# Temp_Controller.net
KiCad netlist of a schematic drawn in EAGLE
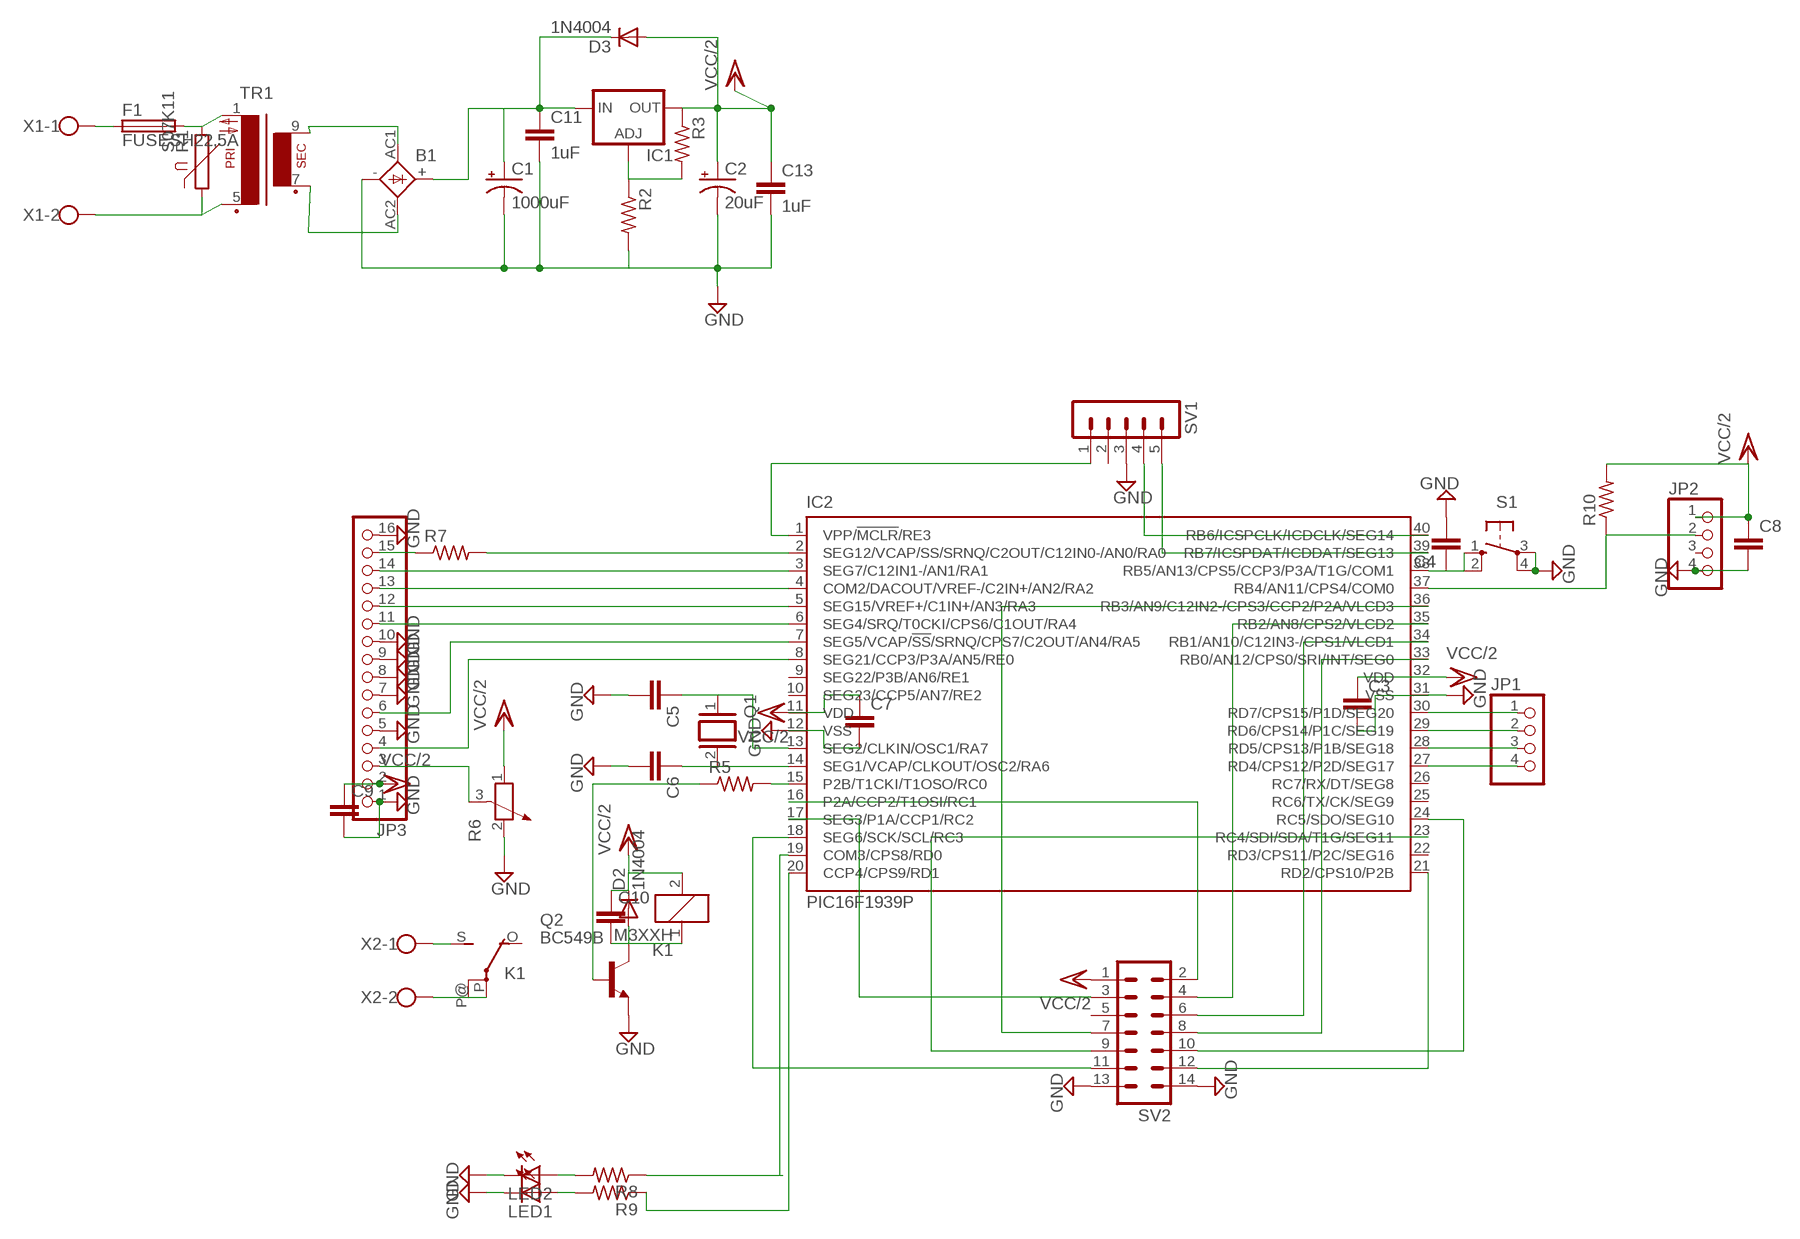
[diagram p0: schematic, sheet 1]

(export (version "E")
  (design (tool "Eeschema 10.0.6"))
  (components
    (comp (ref "B1")
      (value "1KAB")
      (footprint "eagle-import:1KAB")
      (libsource (lib "eagle-import") (part "1KAB"))
    )
    (comp (ref "C1")
      (value "1000uF")
      (footprint "eagle-import:E5-13")
      (libsource (lib "eagle-import") (part "CPOL-USE5-13"))
    )
    (comp (ref "C2")
      (value "20uF")
      (footprint "eagle-import:E5-6")
      (libsource (lib "eagle-import") (part "CPOL-USE5-6"))
    )
    (comp (ref "C3")
      (value "C-EU025-030X050")
      (footprint "eagle-import:C025-030X050")
      (libsource (lib "eagle-import") (part "C-EU025-030X050"))
    )
    (comp (ref "C4")
      (value "C-EU025-030X050")
      (footprint "eagle-import:C025-030X050")
      (libsource (lib "eagle-import") (part "C-EU025-030X050"))
    )
    (comp (ref "C5")
      (value "C2.5/2")
      (footprint "eagle-import:C2.5-2")
      (libsource (lib "eagle-import") (part "C2.5/2"))
    )
    (comp (ref "C6")
      (value "C2.5/2")
      (footprint "eagle-import:C2.5-2")
      (libsource (lib "eagle-import") (part "C2.5/2"))
    )
    (comp (ref "C7")
      (value "C-EU025-030X050")
      (footprint "eagle-import:C025-030X050")
      (libsource (lib "eagle-import") (part "C-EU025-030X050"))
    )
    (comp (ref "C8")
      (value "C-EU025-030X050")
      (footprint "eagle-import:C025-030X050")
      (libsource (lib "eagle-import") (part "C-EU025-030X050"))
    )
    (comp (ref "C9")
      (value "C-EU025-030X050")
      (footprint "eagle-import:C025-030X050")
      (libsource (lib "eagle-import") (part "C-EU025-030X050"))
    )
    (comp (ref "C10")
      (value "C-EU025-030X050")
      (footprint "eagle-import:C025-030X050")
      (libsource (lib "eagle-import") (part "C-EU025-030X050"))
    )
    (comp (ref "C11")
      (value "1uF")
      (footprint "eagle-import:C025-030X050")
      (libsource (lib "eagle-import") (part "C-EU025-030X050"))
    )
    (comp (ref "C13")
      (value "1uF")
      (footprint "eagle-import:C025-030X050")
      (libsource (lib "eagle-import") (part "C-EU025-030X050"))
    )
    (comp (ref "D2")
      (value "1N4004")
      (footprint "eagle-import:DO41-10")
      (libsource (lib "eagle-import") (part "1N4004"))
    )
    (comp (ref "D3")
      (value "1N4004")
      (footprint "eagle-import:DO41-10")
      (libsource (lib "eagle-import") (part "1N4004"))
    )
    (comp (ref "F1")
      (value "FUSESH22,5A")
      (footprint "eagle-import:SH22,5A")
      (fields (field (name "OC_FARNELL") "unknown") (field (name "OC_NEWARK") "unknown"))
      (libsource (lib "eagle-import") (part "FUSESH22,5A"))
    )
    (comp (ref "IC1")
      (value "LM317TS")
      (footprint "eagle-import:317TS")
      (libsource (lib "eagle-import") (part "LM317TS"))
    )
    (comp (ref "IC2")
      (value "PIC16F1939P")
      (footprint "eagle-import:DIL40")
      (libsource (lib "eagle-import") (part "PIC16F193?P9"))
    )
    (comp (ref "JP1")
      (value "PINHD-1X4")
      (footprint "eagle-import:1X04")
      (libsource (lib "eagle-import") (part "PINHD-1X4"))
    )
    (comp (ref "JP2")
      (value "PINHD-1X4")
      (footprint "eagle-import:1X04")
      (libsource (lib "eagle-import") (part "PINHD-1X4"))
    )
    (comp (ref "JP3")
      (value "PINHD-1X16")
      (footprint "eagle-import:1X16")
      (libsource (lib "eagle-import") (part "PINHD-1X16"))
    )
    (comp (ref "K1")
      (value "M3XXH")
      (footprint "eagle-import:M3XXH")
      (libsource (lib "eagle-import") (part "M3XXH"))
    )
    (comp (ref "LED1")
      (value "LED3MM")
      (footprint "eagle-import:LED3MM")
      (libsource (lib "eagle-import") (part "LED3MM"))
    )
    (comp (ref "LED2")
      (value "LED3MM")
      (footprint "eagle-import:LED3MM")
      (libsource (lib "eagle-import") (part "LED3MM"))
    )
    (comp (ref "Q1")
      (value "XTAL/S")
      (footprint "eagle-import:QS")
      (libsource (lib "eagle-import") (part "XTAL/S"))
    )
    (comp (ref "Q2")
      (value "BC549B")
      (footprint "eagle-import:TO92-EBC")
      (libsource (lib "eagle-import") (part "BC549B"))
    )
    (comp (ref "R1")
      (value "S07K11")
      (footprint "eagle-import:S07K11")
      (libsource (lib "eagle-import") (part "S07K11"))
    )
    (comp (ref "R2")
      (value "R-US_0207/10")
      (footprint "eagle-import:0207_10")
      (libsource (lib "eagle-import") (part "R-US_0207/10"))
    )
    (comp (ref "R3")
      (value "R-US_0207/10")
      (footprint "eagle-import:0207_10")
      (libsource (lib "eagle-import") (part "R-US_0207/10"))
    )
    (comp (ref "R5")
      (value "R-US_0207/10")
      (footprint "eagle-import:0207_10")
      (libsource (lib "eagle-import") (part "R-US_0207/10"))
    )
    (comp (ref "R6")
      (value "POTENTIOMETER_PT-10")
      (footprint "eagle-import:PT-10")
      (libsource (lib "eagle-import") (part "POTENTIOMETER_PT-10"))
    )
    (comp (ref "R7")
      (value "R-US_0207/10")
      (footprint "eagle-import:0207_10")
      (libsource (lib "eagle-import") (part "R-US_0207/10"))
    )
    (comp (ref "R8")
      (value "R-US_0207/10")
      (footprint "eagle-import:0207_10")
      (libsource (lib "eagle-import") (part "R-US_0207/10"))
    )
    (comp (ref "R9")
      (value "R-US_0207/10")
      (footprint "eagle-import:0207_10")
      (libsource (lib "eagle-import") (part "R-US_0207/10"))
    )
    (comp (ref "R10")
      (value "R-US_0207/10")
      (footprint "eagle-import:0207_10")
      (libsource (lib "eagle-import") (part "R-US_0207/10"))
    )
    (comp (ref "S1")
      (value "10-XX")
      (footprint "eagle-import:B3F-10XX")
      (libsource (lib "eagle-import") (part "10-XX"))
    )
    (comp (ref "SV1")
      (value "MA05-1")
      (footprint "eagle-import:MA05-1")
      (libsource (lib "eagle-import") (part "MA05-1"))
    )
    (comp (ref "SV2")
      (value "MA07-2")
      (footprint "eagle-import:MA07-2")
      (libsource (lib "eagle-import") (part "MA07-2"))
    )
    (comp (ref "TR1")
      (value "VV11")
      (footprint "eagle-import:VV11")
      (libsource (lib "eagle-import") (part "VV11"))
    )
    (comp (ref "X1")
      (value "W237-02P")
      (footprint "eagle-import:W237-132")
      (libsource (lib "eagle-import") (part "W237-02P"))
    )
    (comp (ref "X2")
      (value "W237-02P")
      (footprint "eagle-import:W237-132")
      (libsource (lib "eagle-import") (part "W237-02P"))
    )
  )
  (nets
    (net (code "1") (name "GND") (class "Default")
      (node (ref "B1") (pin "-") (pinfunction "-_-") (pintype "passive"))
      (node (ref "C1") (pin "-") (pinfunction "-_-") (pintype "passive"))
      (node (ref "C11") (pin "2") (pinfunction "2_2") (pintype "passive"))
      (node (ref "C13") (pin "2") (pinfunction "2_2") (pintype "passive"))
      (node (ref "C2") (pin "-") (pinfunction "-_-") (pintype "passive"))
      (node (ref "C3") (pin "2") (pinfunction "2_2") (pintype "passive"))
      (node (ref "C4") (pin "2") (pinfunction "2_2") (pintype "passive"))
      (node (ref "C5") (pin "2") (pinfunction "2_2") (pintype "passive"))
      (node (ref "C6") (pin "2") (pinfunction "2_2") (pintype "passive"))
      (node (ref "C7") (pin "2") (pinfunction "2_2") (pintype "passive"))
      (node (ref "C8") (pin "2") (pinfunction "2_2") (pintype "passive"))
      (node (ref "C9") (pin "2") (pinfunction "2_2") (pintype "passive"))
      (node (ref "IC2") (pin "12") (pinfunction "VSS_12") (pintype "power_in"))
      (node (ref "IC2") (pin "31") (pinfunction "VSS_31") (pintype "power_in"))
      (node (ref "JP2") (pin "4") (pinfunction "4_4") (pintype "passive"))
      (node (ref "JP3") (pin "1") (pinfunction "1_1") (pintype "passive"))
      (node (ref "JP3") (pin "10") (pinfunction "10_10") (pintype "passive"))
      (node (ref "JP3") (pin "16") (pinfunction "16_16") (pintype "passive"))
      (node (ref "JP3") (pin "5") (pinfunction "5_5") (pintype "passive"))
      (node (ref "JP3") (pin "7") (pinfunction "7_7") (pintype "passive"))
      (node (ref "JP3") (pin "8") (pinfunction "8_8") (pintype "passive"))
      (node (ref "JP3") (pin "9") (pinfunction "9_9") (pintype "passive"))
      (node (ref "LED1") (pin "K") (pinfunction "C_K") (pintype "passive"))
      (node (ref "LED2") (pin "K") (pinfunction "C_K") (pintype "passive"))
      (node (ref "Q2") (pin "E") (pinfunction "E_E") (pintype "passive"))
      (node (ref "R2") (pin "2") (pinfunction "2_2") (pintype "passive"))
      (node (ref "R6") (pin "2") (pinfunction "2_2") (pintype "passive"))
      (node (ref "S1") (pin "3") (pinfunction "P_3") (pintype "passive"))
      (node (ref "S1") (pin "4") (pinfunction "P1_4") (pintype "passive"))
      (node (ref "SV1") (pin "3") (pinfunction "3_3") (pintype "passive"))
      (node (ref "SV2") (pin "13") (pinfunction "13_13") (pintype "passive"))
      (node (ref "SV2") (pin "14") (pinfunction "14_14") (pintype "passive"))
    )
    (net (code "2") (name "Net-(C10-Pad2)") (class "Default")
      (node (ref "C10") (pin "2") (pinfunction "2_2") (pintype "passive"))
      (node (ref "D2") (pin "A") (pinfunction "A_A") (pintype "passive"))
      (node (ref "K1") (pin "1") (pinfunction "1_1") (pintype "passive"))
      (node (ref "Q2") (pin "C") (pinfunction "C_C") (pintype "passive"))
    )
    (net (code "3") (name "Net-(IC1-ADJ)") (class "Default")
      (node (ref "IC1") (pin "1") (pinfunction "ADJ_1") (pintype "input"))
      (node (ref "R2") (pin "1") (pinfunction "1_1") (pintype "passive"))
      (node (ref "R3") (pin "2") (pinfunction "2_2") (pintype "passive"))
    )
    (net (code "4") (name "Net-(IC1-IN)") (class "Default")
      (node (ref "B1") (pin "+") (pinfunction "+_+") (pintype "passive"))
      (node (ref "C1") (pin "+") (pinfunction "+_+") (pintype "passive"))
      (node (ref "C11") (pin "1") (pinfunction "1_1") (pintype "passive"))
      (node (ref "D3") (pin "C") (pinfunction "C_C") (pintype "passive"))
      (node (ref "IC1") (pin "3") (pinfunction "IN_3") (pintype "input"))
    )
    (net (code "5") (name "Net-(IC2-CCP4{slash}CPS9{slash}RD1)") (class "Default")
      (node (ref "IC2") (pin "20") (pinfunction "CCP4/CPS9/RD1_20") (pintype "bidirectional"))
      (node (ref "R9") (pin "1") (pinfunction "1_1") (pintype "passive"))
    )
    (net (code "6") (name "Net-(IC2-COM2{slash}DACOUT{slash}VREF-{slash}C2IN+{slash}AN2{slash}RA2)") (class "Default")
      (node (ref "IC2") (pin "4") (pinfunction "COM2/DACOUT/VREF-/C2IN+/AN2/RA2_4") (pintype "bidirectional"))
      (node (ref "JP3") (pin "13") (pinfunction "13_13") (pintype "passive"))
    )
    (net (code "7") (name "Net-(IC2-COM3{slash}CPS8{slash}RD0)") (class "Default")
      (node (ref "IC2") (pin "19") (pinfunction "COM3/CPS8/RD0_19") (pintype "bidirectional"))
      (node (ref "R8") (pin "1") (pinfunction "1_1") (pintype "passive"))
    )
    (net (code "8") (name "Net-(IC2-P2A{slash}CCP2{slash}T1OSI{slash}RC1)") (class "Default")
      (node (ref "IC2") (pin "16") (pinfunction "P2A/CCP2/T1OSI/RC1_16") (pintype "bidirectional"))
      (node (ref "SV2") (pin "2") (pinfunction "2_2") (pintype "passive"))
    )
    (net (code "9") (name "Net-(IC2-P2B{slash}T1CKI{slash}T1OSO{slash}RC0)") (class "Default")
      (node (ref "IC2") (pin "15") (pinfunction "P2B/T1CKI/T1OSO/RC0_15") (pintype "bidirectional"))
      (node (ref "R5") (pin "2") (pinfunction "2_2") (pintype "passive"))
    )
    (net (code "10") (name "Net-(IC2-RB0{slash}AN12{slash}CPS0{slash}SRI{slash}INT{slash}SEG0)") (class "Default")
      (node (ref "IC2") (pin "33") (pinfunction "RB0/AN12/CPS0/SRI/INT/SEG0_33") (pintype "bidirectional"))
      (node (ref "SV2") (pin "8") (pinfunction "8_8") (pintype "passive"))
    )
    (net (code "11") (name "Net-(IC2-RB1{slash}AN10{slash}C12IN3-{slash}CPS1{slash}VLCD1)") (class "Default")
      (node (ref "IC2") (pin "34") (pinfunction "RB1/AN10/C12IN3-/CPS1/VLCD1_34") (pintype "bidirectional"))
      (node (ref "SV2") (pin "6") (pinfunction "6_6") (pintype "passive"))
    )
    (net (code "12") (name "Net-(IC2-RB2{slash}AN8{slash}CPS2{slash}VLCD2)") (class "Default")
      (node (ref "IC2") (pin "35") (pinfunction "RB2/AN8/CPS2/VLCD2_35") (pintype "bidirectional"))
      (node (ref "SV2") (pin "4") (pinfunction "4_4") (pintype "passive"))
    )
    (net (code "13") (name "Net-(IC2-RB3{slash}AN9{slash}C12IN2-{slash}CPS3{slash}CCP2{slash}P2A{slash}VLCD3)") (class "Default")
      (node (ref "IC2") (pin "36") (pinfunction "RB3/AN9/C12IN2-/CPS3/CCP2/P2A/VLCD3_36") (pintype "bidirectional"))
      (node (ref "SV2") (pin "7") (pinfunction "7_7") (pintype "passive"))
    )
    (net (code "14") (name "Net-(IC2-RB4{slash}AN11{slash}CPS4{slash}COM0)") (class "Default")
      (node (ref "IC2") (pin "37") (pinfunction "RB4/AN11/CPS4/COM0_37") (pintype "bidirectional"))
      (node (ref "JP2") (pin "2") (pinfunction "2_2") (pintype "passive"))
      (node (ref "R10") (pin "1") (pinfunction "1_1") (pintype "passive"))
    )
    (net (code "15") (name "Net-(IC2-RB5{slash}AN13{slash}CPS5{slash}CCP3{slash}P3A{slash}T1G{slash}COM1)") (class "Default")
      (node (ref "C4") (pin "1") (pinfunction "1_1") (pintype "passive"))
      (node (ref "IC2") (pin "38") (pinfunction "RB5/AN13/CPS5/CCP3/P3A/T1G/COM1_38") (pintype "bidirectional"))
      (node (ref "S1") (pin "1") (pinfunction "S_1") (pintype "passive"))
      (node (ref "S1") (pin "2") (pinfunction "S1_2") (pintype "passive"))
    )
    (net (code "16") (name "Net-(IC2-RB6{slash}ICSPCLK{slash}ICDCLK{slash}SEG14)") (class "Default")
      (node (ref "IC2") (pin "40") (pinfunction "RB6/ICSPCLK/ICDCLK/SEG14_40") (pintype "bidirectional"))
      (node (ref "SV1") (pin "4") (pinfunction "4_4") (pintype "passive"))
    )
    (net (code "17") (name "Net-(IC2-RB7{slash}ICSPDAT{slash}ICDDAT{slash}SEG13)") (class "Default")
      (node (ref "IC2") (pin "39") (pinfunction "RB7/ICSPDAT/ICDDAT/SEG13_39") (pintype "bidirectional"))
      (node (ref "SV1") (pin "5") (pinfunction "5_5") (pintype "passive"))
    )
    (net (code "18") (name "Net-(IC2-RC4{slash}SDI{slash}SDA{slash}T1G{slash}SEG11)") (class "Default")
      (node (ref "IC2") (pin "23") (pinfunction "RC4/SDI/SDA/T1G/SEG11_23") (pintype "bidirectional"))
      (node (ref "SV2") (pin "9") (pinfunction "9_9") (pintype "passive"))
    )
    (net (code "19") (name "Net-(IC2-RC5{slash}SDO{slash}SEG10)") (class "Default")
      (node (ref "IC2") (pin "24") (pinfunction "RC5/SDO/SEG10_24") (pintype "bidirectional"))
      (node (ref "SV2") (pin "10") (pinfunction "10_10") (pintype "passive"))
    )
    (net (code "20") (name "Net-(IC2-RD2{slash}CPS10{slash}P2B)") (class "Default")
      (node (ref "IC2") (pin "21") (pinfunction "RD2/CPS10/P2B_21") (pintype "bidirectional"))
      (node (ref "SV2") (pin "12") (pinfunction "12_12") (pintype "passive"))
    )
    (net (code "21") (name "Net-(IC2-RD4{slash}CPS12{slash}P2D{slash}SEG17)") (class "Default")
      (node (ref "IC2") (pin "27") (pinfunction "RD4/CPS12/P2D/SEG17_27") (pintype "bidirectional"))
      (node (ref "JP1") (pin "4") (pinfunction "4_4") (pintype "passive"))
    )
    (net (code "22") (name "Net-(IC2-RD5{slash}CPS13{slash}P1B{slash}SEG18)") (class "Default")
      (node (ref "IC2") (pin "28") (pinfunction "RD5/CPS13/P1B/SEG18_28") (pintype "bidirectional"))
      (node (ref "JP1") (pin "3") (pinfunction "3_3") (pintype "passive"))
    )
    (net (code "23") (name "Net-(IC2-RD6{slash}CPS14{slash}P1C{slash}SEG19)") (class "Default")
      (node (ref "IC2") (pin "29") (pinfunction "RD6/CPS14/P1C/SEG19_29") (pintype "bidirectional"))
      (node (ref "JP1") (pin "2") (pinfunction "2_2") (pintype "passive"))
    )
    (net (code "24") (name "Net-(IC2-RD7{slash}CPS15{slash}P1D{slash}SEG20)") (class "Default")
      (node (ref "IC2") (pin "30") (pinfunction "RD7/CPS15/P1D/SEG20_30") (pintype "bidirectional"))
      (node (ref "JP1") (pin "1") (pinfunction "1_1") (pintype "passive"))
    )
    (net (code "25") (name "Net-(IC2-SEG1{slash}VCAP{slash}CLKOUT{slash}OSC2{slash}RA6)") (class "Default")
      (node (ref "C6") (pin "1") (pinfunction "1_1") (pintype "passive"))
      (node (ref "IC2") (pin "14") (pinfunction "SEG1/VCAP/CLKOUT/OSC2/RA6_14") (pintype "bidirectional"))
      (node (ref "Q1") (pin "2") (pinfunction "2_2") (pintype "passive"))
    )
    (net (code "26") (name "Net-(IC2-SEG2{slash}CLKIN{slash}OSC1{slash}RA7)") (class "Default")
      (node (ref "C5") (pin "1") (pinfunction "1_1") (pintype "passive"))
      (node (ref "IC2") (pin "13") (pinfunction "SEG2/CLKIN/OSC1/RA7_13") (pintype "bidirectional"))
      (node (ref "Q1") (pin "1") (pinfunction "1_1") (pintype "passive"))
    )
    (net (code "27") (name "Net-(IC2-SEG3{slash}P1A{slash}CCP1{slash}RC2)") (class "Default")
      (node (ref "IC2") (pin "17") (pinfunction "SEG3/P1A/CCP1/RC2_17") (pintype "bidirectional"))
      (node (ref "SV2") (pin "3") (pinfunction "3_3") (pintype "passive"))
    )
    (net (code "28") (name "Net-(IC2-SEG4{slash}SRQ{slash}T0CKI{slash}CPS6{slash}C1OUT{slash}RA4)") (class "Default")
      (node (ref "IC2") (pin "6") (pinfunction "SEG4/SRQ/T0CKI/CPS6/C1OUT/RA4_6") (pintype "bidirectional"))
      (node (ref "JP3") (pin "11") (pinfunction "11_11") (pintype "passive"))
    )
    (net (code "29") (name "Net-(IC2-SEG5{slash}VCAP{slash}~{SS}{slash}SRNQ{slash}CPS7{slash}C2OUT{slash}AN4{slash}RA5)") (class "Default")
      (node (ref "IC2") (pin "7") (pinfunction "SEG5/VCAP/~{SS}/SRNQ/CPS7/C2OUT/AN4/RA5_7") (pintype "bidirectional"))
      (node (ref "JP3") (pin "6") (pinfunction "6_6") (pintype "passive"))
    )
    (net (code "30") (name "Net-(IC2-SEG6{slash}SCK{slash}SCL{slash}RC3)") (class "Default")
      (node (ref "IC2") (pin "18") (pinfunction "SEG6/SCK/SCL/RC3_18") (pintype "bidirectional"))
      (node (ref "SV2") (pin "11") (pinfunction "11_11") (pintype "passive"))
    )
    (net (code "31") (name "Net-(IC2-SEG7{slash}C12IN1-{slash}AN1{slash}RA1)") (class "Default")
      (node (ref "IC2") (pin "3") (pinfunction "SEG7/C12IN1-/AN1/RA1_3") (pintype "bidirectional"))
      (node (ref "JP3") (pin "14") (pinfunction "14_14") (pintype "passive"))
    )
    (net (code "32") (name "Net-(IC2-SEG12{slash}VCAP{slash}SS{slash}SRNQ{slash}C2OUT{slash}C12IN0-{slash}AN0{slash}RA0)") (class "Default")
      (node (ref "IC2") (pin "2") (pinfunction "SEG12/VCAP/SS/SRNQ/C2OUT/C12IN0-/AN0/RA0_2") (pintype "bidirectional"))
      (node (ref "R7") (pin "2") (pinfunction "2_2") (pintype "passive"))
    )
    (net (code "33") (name "Net-(IC2-SEG15{slash}VREF+{slash}C1IN+{slash}AN3{slash}RA3)") (class "Default")
      (node (ref "IC2") (pin "5") (pinfunction "SEG15/VREF+/C1IN+/AN3/RA3_5") (pintype "bidirectional"))
      (node (ref "JP3") (pin "12") (pinfunction "12_12") (pintype "passive"))
    )
    (net (code "34") (name "Net-(IC2-SEG21{slash}CCP3{slash}P3A{slash}AN5{slash}RE0)") (class "Default")
      (node (ref "IC2") (pin "8") (pinfunction "SEG21/CCP3/P3A/AN5/RE0_8") (pintype "bidirectional"))
      (node (ref "JP3") (pin "4") (pinfunction "4_4") (pintype "passive"))
    )
    (net (code "35") (name "Net-(IC2-VPP{slash}~{MCLR}{slash}RE3)") (class "Default")
      (node (ref "IC2") (pin "1") (pinfunction "VPP/~{MCLR}/RE3_1") (pintype "input"))
      (node (ref "SV1") (pin "1") (pinfunction "1_1") (pintype "passive"))
    )
    (net (code "36") (name "Net-(JP3-Pad3)") (class "Default")
      (node (ref "JP3") (pin "3") (pinfunction "3_3") (pintype "passive"))
      (node (ref "R6") (pin "3") (pinfunction "3_3") (pintype "passive"))
    )
    (net (code "37") (name "Net-(JP3-Pad15)") (class "Default")
      (node (ref "JP3") (pin "15") (pinfunction "15_15") (pintype "passive"))
      (node (ref "R7") (pin "1") (pinfunction "1_1") (pintype "passive"))
    )
    (net (code "38") (name "Net-(LED1-PadA)") (class "Default")
      (node (ref "LED1") (pin "A") (pinfunction "A_A") (pintype "passive"))
      (node (ref "R9") (pin "2") (pinfunction "2_2") (pintype "passive"))
    )
    (net (code "39") (name "Net-(LED2-PadA)") (class "Default")
      (node (ref "LED2") (pin "A") (pinfunction "A_A") (pintype "passive"))
      (node (ref "R8") (pin "2") (pinfunction "2_2") (pintype "passive"))
    )
    (net (code "40") (name "Net-(Q2-PadB)") (class "Default")
      (node (ref "Q2") (pin "B") (pinfunction "B_B") (pintype "passive"))
      (node (ref "R5") (pin "1") (pinfunction "1_1") (pintype "passive"))
    )
    (net (code "41") (name "Net-(TR1-P1)") (class "Default")
      (node (ref "F1") (pin "2") (pinfunction "2_2") (pintype "passive"))
      (node (ref "R1") (pin "2") (pinfunction "2_2") (pintype "passive"))
      (node (ref "TR1") (pin "1") (pinfunction "P1_1") (pintype "passive"))
    )
    (net (code "42") (name "Net-(TR1-P2)") (class "Default")
      (node (ref "R1") (pin "1") (pinfunction "1_1") (pintype "passive"))
      (node (ref "TR1") (pin "5") (pinfunction "P2_5") (pintype "passive"))
      (node (ref "X1") (pin "2") (pinfunction "KL_2") (pintype "passive"))
    )
    (net (code "43") (name "Net-(TR1-S3)") (class "Default")
      (node (ref "B1") (pin "AC2") (pinfunction "AC2_AC2") (pintype "passive"))
      (node (ref "TR1") (pin "7") (pinfunction "S3_7") (pintype "passive"))
    )
    (net (code "44") (name "Net-(TR1-S4)") (class "Default")
      (node (ref "B1") (pin "AC1") (pinfunction "AC1_AC1") (pintype "passive"))
      (node (ref "TR1") (pin "9") (pinfunction "S4_9") (pintype "passive"))
    )
    (net (code "45") (name "Net-(X1A-KL)") (class "Default")
      (node (ref "F1") (pin "1") (pinfunction "1_1") (pintype "passive"))
      (node (ref "X1") (pin "1") (pinfunction "KL_1") (pintype "passive"))
    )
    (net (code "46") (name "Net-(X2A-KL)") (class "Default")
      (node (ref "K1") (pin "S") (pinfunction "S_S") (pintype "passive"))
      (node (ref "X2") (pin "1") (pinfunction "KL_1") (pintype "passive"))
    )
    (net (code "47") (name "Net-(X2B-KL)") (class "Default")
      (node (ref "K1") (pin "P") (pinfunction "P_P") (pintype "passive"))
      (node (ref "K1") (pin "P@") (pinfunction "P_P@") (pintype "passive"))
      (node (ref "X2") (pin "2") (pinfunction "KL_2") (pintype "passive"))
    )
    (net (code "48") (name "VCC{slash}2") (class "Default")
      (node (ref "C10") (pin "1") (pinfunction "1_1") (pintype "passive"))
      (node (ref "C13") (pin "1") (pinfunction "1_1") (pintype "passive"))
      (node (ref "C2") (pin "+") (pinfunction "+_+") (pintype "passive"))
      (node (ref "C3") (pin "1") (pinfunction "1_1") (pintype "passive"))
      (node (ref "C7") (pin "1") (pinfunction "1_1") (pintype "passive"))
      (node (ref "C8") (pin "1") (pinfunction "1_1") (pintype "passive"))
      (node (ref "C9") (pin "1") (pinfunction "1_1") (pintype "passive"))
      (node (ref "D2") (pin "C") (pinfunction "C_C") (pintype "passive"))
      (node (ref "D3") (pin "A") (pinfunction "A_A") (pintype "passive"))
      (node (ref "IC1") (pin "2") (pinfunction "OUT_2") (pintype "passive"))
      (node (ref "IC2") (pin "11") (pinfunction "VDD_11") (pintype "power_in"))
      (node (ref "IC2") (pin "32") (pinfunction "VDD_32") (pintype "power_in"))
      (node (ref "JP2") (pin "1") (pinfunction "1_1") (pintype "passive"))
      (node (ref "JP3") (pin "2") (pinfunction "2_2") (pintype "passive"))
      (node (ref "K1") (pin "2") (pinfunction "2_2") (pintype "passive"))
      (node (ref "R10") (pin "2") (pinfunction "2_2") (pintype "passive"))
      (node (ref "R3") (pin "1") (pinfunction "1_1") (pintype "passive"))
      (node (ref "R6") (pin "1") (pinfunction "1_1") (pintype "passive"))
      (node (ref "SV2") (pin "1") (pinfunction "1_1") (pintype "passive"))
    )
    (net (code "49") (name "unconnected-(IC2-RC6{slash}TX{slash}CK{slash}SEG9-Pad25)") (class "Default")
      (node (ref "IC2") (pin "25") (pinfunction "RC6/TX/CK/SEG9_25") (pintype "bidirectional"))
    )
    (net (code "50") (name "unconnected-(IC2-RC7{slash}RX{slash}DT{slash}SEG8-Pad26)") (class "Default")
      (node (ref "IC2") (pin "26") (pinfunction "RC7/RX/DT/SEG8_26") (pintype "bidirectional"))
    )
    (net (code "51") (name "unconnected-(IC2-RD3{slash}CPS11{slash}P2C{slash}SEG16-Pad22)") (class "Default")
      (node (ref "IC2") (pin "22") (pinfunction "RD3/CPS11/P2C/SEG16_22") (pintype "bidirectional"))
    )
    (net (code "52") (name "unconnected-(IC2-SEG22{slash}P3B{slash}AN6{slash}RE1-Pad9)") (class "Default")
      (node (ref "IC2") (pin "9") (pinfunction "SEG22/P3B/AN6/RE1_9") (pintype "bidirectional"))
    )
    (net (code "53") (name "unconnected-(IC2-SEG23{slash}CCP5{slash}AN7{slash}RE2-Pad10)") (class "Default")
      (node (ref "IC2") (pin "10") (pinfunction "SEG23/CCP5/AN7/RE2_10") (pintype "bidirectional"))
    )
    (net (code "54") (name "unconnected-(JP2-Pad3)") (class "Default")
      (node (ref "JP2") (pin "3") (pinfunction "3_3") (pintype "passive"))
    )
    (net (code "55") (name "unconnected-(K1-PadO)") (class "Default")
      (node (ref "K1") (pin "O") (pinfunction "O_O") (pintype "passive"))
    )
    (net (code "56") (name "unconnected-(SV1-Pad2)") (class "Default")
      (node (ref "SV1") (pin "2") (pinfunction "2_2") (pintype "passive"))
    )
    (net (code "57") (name "unconnected-(SV2-Pad5)") (class "Default")
      (node (ref "SV2") (pin "5") (pinfunction "5_5") (pintype "passive"))
    )
  )
)
